# smallDevV1.net
KiCad netlist of a schematic drawn in EAGLE
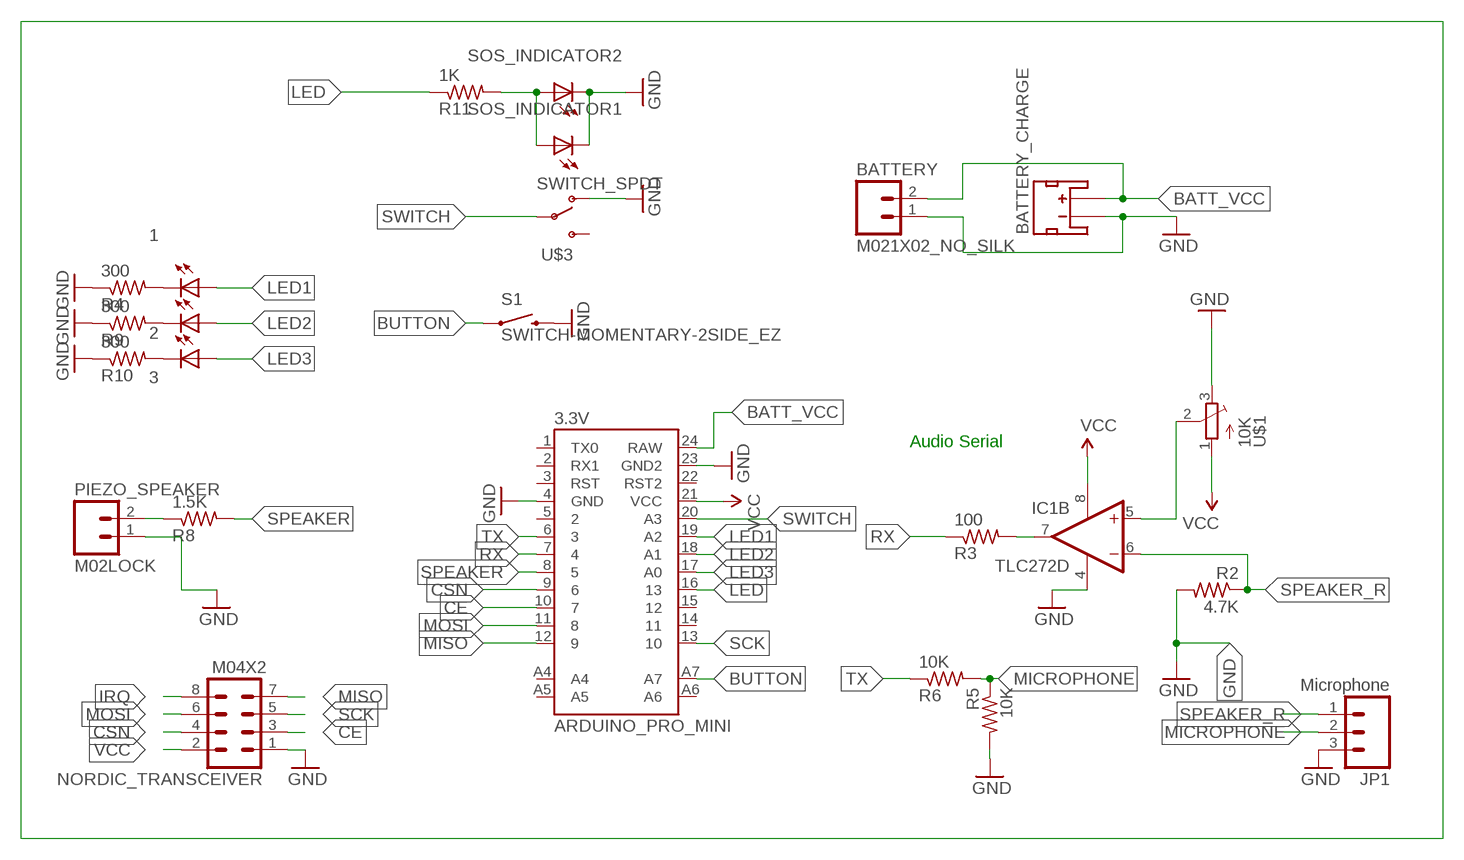
[diagram p0: schematic, sheet 1]

(export (version "E")
  (design (tool "Eeschema 10.0.6"))
  (components
    (comp (ref "1")
      (value "LEDCHIP-LED0805")
      (footprint "eagle-import:CHIP-LED0805")
      (libsource (lib "eagle-import") (part "LEDCHIP-LED0805"))
    )
    (comp (ref "2")
      (value "LEDCHIP-LED0805")
      (footprint "eagle-import:CHIP-LED0805")
      (libsource (lib "eagle-import") (part "LEDCHIP-LED0805"))
    )
    (comp (ref "3")
      (value "LEDCHIP-LED0805")
      (footprint "eagle-import:CHIP-LED0805")
      (libsource (lib "eagle-import") (part "LEDCHIP-LED0805"))
    )
    (comp (ref "3.3V")
      (value "ARDUINO_PRO_MINI")
      (footprint "eagle-import:ARDUINO_PRO_MINI_NO_PROGRAMMING_HEADER")
      (libsource (lib "eagle-import") (part "ARDUINO_PRO_MINI"))
    )
    (comp (ref "BATTERY")
      (value "M021X02_NO_SILK")
      (footprint "eagle-import:1X02_NO_SILK")
      (libsource (lib "eagle-import") (part "M021X02_NO_SILK"))
    )
    (comp (ref "BATTERY_CHARGE")
      (value "JST_2MM_MALE")
      (footprint "eagle-import:JST-2-SMD")
      (libsource (lib "eagle-import") (part "JST_2MM_MALE"))
    )
    (comp (ref "IC1")
      (value "TLC272D")
      (footprint "eagle-import:SO08")
      (libsource (lib "eagle-import") (part "TLC272D"))
    )
    (comp (ref "JP1")
      (value "Microphone")
      (footprint "eagle-import:1X03_LOCK")
      (libsource (lib "eagle-import") (part "M03LOCK"))
    )
    (comp (ref "NORDIC_TRANSCEIVER")
      (value "M04X2")
      (footprint "eagle-import:2X4")
      (libsource (lib "eagle-import") (part "M04X2"))
    )
    (comp (ref "PIEZO_SPEAKER")
      (value "M02LOCK")
      (footprint "eagle-import:1X02_LOCK")
      (libsource (lib "eagle-import") (part "M02LOCK"))
    )
    (comp (ref "R2")
      (value "4.7K")
      (footprint "eagle-import:M0805")
      (libsource (lib "eagle-import") (part "R-US_M0805"))
    )
    (comp (ref "R3")
      (value "100")
      (footprint "eagle-import:M0805")
      (libsource (lib "eagle-import") (part "R-US_M0805"))
    )
    (comp (ref "R4")
      (value "300")
      (footprint "eagle-import:M0805")
      (libsource (lib "eagle-import") (part "R-US_M0805"))
    )
    (comp (ref "R5")
      (value "10K")
      (footprint "eagle-import:M0805")
      (libsource (lib "eagle-import") (part "R-US_M0805"))
    )
    (comp (ref "R6")
      (value "10K")
      (footprint "eagle-import:M0805")
      (libsource (lib "eagle-import") (part "R-US_M0805"))
    )
    (comp (ref "R8")
      (value "1.5K")
      (footprint "eagle-import:M0805")
      (libsource (lib "eagle-import") (part "R-US_M0805"))
    )
    (comp (ref "R9")
      (value "300")
      (footprint "eagle-import:M0805")
      (libsource (lib "eagle-import") (part "R-US_M0805"))
    )
    (comp (ref "R10")
      (value "300")
      (footprint "eagle-import:M0805")
      (libsource (lib "eagle-import") (part "R-US_M0805"))
    )
    (comp (ref "R11")
      (value "1K")
      (footprint "eagle-import:M0805")
      (libsource (lib "eagle-import") (part "R-US_M0805"))
    )
    (comp (ref "S1")
      (value "SWITCH-MOMENTARY-2SIDE_EZ")
      (footprint "eagle-import:TACTILE-PTH-SIDEEZ")
      (libsource (lib "eagle-import") (part "SWITCH-MOMENTARY-2SIDE_EZ"))
    )
    (comp (ref "SOS_INDICATOR1")
      (value "LEDCHIP-LED0805")
      (footprint "eagle-import:CHIP-LED0805")
      (libsource (lib "eagle-import") (part "LEDCHIP-LED0805"))
    )
    (comp (ref "SOS_INDICATOR2")
      (value "LEDCHIP-LED0805")
      (footprint "eagle-import:CHIP-LED0805")
      (libsource (lib "eagle-import") (part "LEDCHIP-LED0805"))
    )
    (comp (ref "U$1")
      (value "10K")
      (footprint "eagle-import:TC33X")
      (libsource (lib "eagle-import") (part "TRIMPOTTC33X"))
    )
    (comp (ref "U$3")
      (value "SWITCH_SPDT")
      (footprint "eagle-import:SWITCH-SPST-SMD-A-NOTHRUHOLE")
      (libsource (lib "eagle-import") (part "SWITCH_SPDT"))
    )
  )
  (nets
    (net (code "1") (name "BATT_VCC") (class "Default")
      (node (ref "3.3V") (pin "24") (pinfunction "RAW_24") (pintype "bidirectional"))
      (node (ref "BATTERY") (pin "2") (pinfunction "2_2") (pintype "passive"))
      (node (ref "BATTERY_CHARGE") (pin "2") (pinfunction "+_2") (pintype "bidirectional"))
    )
    (net (code "2") (name "BUTTON") (class "Default")
      (node (ref "3.3V") (pin "A7") (pinfunction "A7_A7") (pintype "bidirectional"))
      (node (ref "S1") (pin "1") (pinfunction "1_1") (pintype "passive"))
    )
    (net (code "3") (name "CE") (class "Default")
      (node (ref "3.3V") (pin "10") (pinfunction "7_10") (pintype "bidirectional"))
      (node (ref "NORDIC_TRANSCEIVER") (pin "3") (pinfunction "3_3") (pintype "passive"))
    )
    (net (code "4") (name "CSN") (class "Default")
      (node (ref "3.3V") (pin "9") (pinfunction "6_9") (pintype "bidirectional"))
      (node (ref "NORDIC_TRANSCEIVER") (pin "4") (pinfunction "4_4") (pintype "passive"))
    )
    (net (code "5") (name "GND") (class "Default")
      (node (ref "3.3V") (pin "23") (pinfunction "GND2_23") (pintype "bidirectional"))
      (node (ref "3.3V") (pin "4") (pinfunction "GND_4") (pintype "bidirectional"))
      (node (ref "BATTERY") (pin "1") (pinfunction "1_1") (pintype "passive"))
      (node (ref "BATTERY_CHARGE") (pin "1") (pinfunction "-_1") (pintype "bidirectional"))
      (node (ref "IC1") (pin "4") (pinfunction "V-_4") (pintype "power_in"))
      (node (ref "JP1") (pin "3") (pinfunction "3_3") (pintype "passive"))
      (node (ref "NORDIC_TRANSCEIVER") (pin "1") (pinfunction "1_1") (pintype "passive"))
      (node (ref "PIEZO_SPEAKER") (pin "1") (pinfunction "1_1") (pintype "passive"))
      (node (ref "R10") (pin "1") (pinfunction "1_1") (pintype "passive"))
      (node (ref "R2") (pin "2") (pinfunction "2_2") (pintype "passive"))
      (node (ref "R4") (pin "1") (pinfunction "1_1") (pintype "passive"))
      (node (ref "R5") (pin "2") (pinfunction "2_2") (pintype "passive"))
      (node (ref "R9") (pin "1") (pinfunction "1_1") (pintype "passive"))
      (node (ref "S1") (pin "2") (pinfunction "2_2") (pintype "passive"))
      (node (ref "SOS_INDICATOR1") (pin "C") (pinfunction "C_C") (pintype "passive"))
      (node (ref "SOS_INDICATOR2") (pin "C") (pinfunction "C_C") (pintype "passive"))
      (node (ref "U$1") (pin "3") (pinfunction "E_3") (pintype "passive"))
      (node (ref "U$3") (pin "1") (pinfunction "O_1") (pintype "passive"))
    )
    (net (code "6") (name "IRQ") (class "Default")
      (node (ref "NORDIC_TRANSCEIVER") (pin "8") (pinfunction "8_8") (pintype "passive"))
    )
    (net (code "7") (name "LED") (class "Default")
      (node (ref "3.3V") (pin "16") (pinfunction "13_16") (pintype "bidirectional"))
      (node (ref "R11") (pin "1") (pinfunction "1_1") (pintype "passive"))
    )
    (net (code "8") (name "LED1") (class "Default")
      (node (ref "1") (pin "A") (pinfunction "A_A") (pintype "passive"))
      (node (ref "3.3V") (pin "19") (pinfunction "A2_19") (pintype "bidirectional"))
    )
    (net (code "9") (name "LED2") (class "Default")
      (node (ref "2") (pin "A") (pinfunction "A_A") (pintype "passive"))
      (node (ref "3.3V") (pin "18") (pinfunction "A1_18") (pintype "bidirectional"))
    )
    (net (code "10") (name "LED3") (class "Default")
      (node (ref "3") (pin "A") (pinfunction "A_A") (pintype "passive"))
      (node (ref "3.3V") (pin "17") (pinfunction "A0_17") (pintype "bidirectional"))
    )
    (net (code "11") (name "MICROPHONE") (class "Default")
      (node (ref "JP1") (pin "2") (pinfunction "2_2") (pintype "passive"))
      (node (ref "R5") (pin "1") (pinfunction "1_1") (pintype "passive"))
      (node (ref "R6") (pin "2") (pinfunction "2_2") (pintype "passive"))
    )
    (net (code "12") (name "MISO") (class "Default")
      (node (ref "3.3V") (pin "12") (pinfunction "9_12") (pintype "bidirectional"))
      (node (ref "NORDIC_TRANSCEIVER") (pin "7") (pinfunction "7_7") (pintype "passive"))
    )
    (net (code "13") (name "MOSI") (class "Default")
      (node (ref "3.3V") (pin "11") (pinfunction "8_11") (pintype "bidirectional"))
      (node (ref "NORDIC_TRANSCEIVER") (pin "6") (pinfunction "6_6") (pintype "passive"))
    )
    (net (code "14") (name "Net-(1-PadC)") (class "Default")
      (node (ref "1") (pin "C") (pinfunction "C_C") (pintype "passive"))
      (node (ref "R4") (pin "2") (pinfunction "2_2") (pintype "passive"))
    )
    (net (code "15") (name "Net-(2-PadC)") (class "Default")
      (node (ref "2") (pin "C") (pinfunction "C_C") (pintype "passive"))
      (node (ref "R9") (pin "2") (pinfunction "2_2") (pintype "passive"))
    )
    (net (code "16") (name "Net-(3-PadC)") (class "Default")
      (node (ref "3") (pin "C") (pinfunction "C_C") (pintype "passive"))
      (node (ref "R10") (pin "2") (pinfunction "2_2") (pintype "passive"))
    )
    (net (code "17") (name "Net-(IC1B-+IN)") (class "Default")
      (node (ref "IC1") (pin "5") (pinfunction "+IN_5") (pintype "input"))
      (node (ref "U$1") (pin "2") (pinfunction "S_2") (pintype "passive"))
    )
    (net (code "18") (name "Net-(IC1B-OUT)") (class "Default")
      (node (ref "IC1") (pin "7") (pinfunction "OUT_7") (pintype "output"))
      (node (ref "R3") (pin "2") (pinfunction "2_2") (pintype "passive"))
    )
    (net (code "19") (name "Net-(PIEZO_SPEAKER-Pad2)") (class "Default")
      (node (ref "PIEZO_SPEAKER") (pin "2") (pinfunction "2_2") (pintype "passive"))
      (node (ref "R8") (pin "1") (pinfunction "1_1") (pintype "passive"))
    )
    (net (code "20") (name "Net-(R11-Pad2)") (class "Default")
      (node (ref "R11") (pin "2") (pinfunction "2_2") (pintype "passive"))
      (node (ref "SOS_INDICATOR1") (pin "A") (pinfunction "A_A") (pintype "passive"))
      (node (ref "SOS_INDICATOR2") (pin "A") (pinfunction "A_A") (pintype "passive"))
    )
    (net (code "21") (name "RX") (class "Default")
      (node (ref "3.3V") (pin "7") (pinfunction "4_7") (pintype "bidirectional"))
      (node (ref "R3") (pin "1") (pinfunction "1_1") (pintype "passive"))
    )
    (net (code "22") (name "SCK") (class "Default")
      (node (ref "3.3V") (pin "13") (pinfunction "10_13") (pintype "bidirectional"))
      (node (ref "NORDIC_TRANSCEIVER") (pin "5") (pinfunction "5_5") (pintype "passive"))
    )
    (net (code "23") (name "SPEAKER") (class "Default")
      (node (ref "3.3V") (pin "8") (pinfunction "5_8") (pintype "bidirectional"))
      (node (ref "R8") (pin "2") (pinfunction "2_2") (pintype "passive"))
    )
    (net (code "24") (name "SPEAKER_R") (class "Default")
      (node (ref "IC1") (pin "6") (pinfunction "-IN_6") (pintype "input"))
      (node (ref "JP1") (pin "1") (pinfunction "1_1") (pintype "passive"))
      (node (ref "R2") (pin "1") (pinfunction "1_1") (pintype "passive"))
    )
    (net (code "25") (name "SWITCH") (class "Default")
      (node (ref "3.3V") (pin "20") (pinfunction "A3_20") (pintype "bidirectional"))
      (node (ref "U$3") (pin "2") (pinfunction "P_2") (pintype "passive"))
    )
    (net (code "26") (name "TX") (class "Default")
      (node (ref "3.3V") (pin "6") (pinfunction "3_6") (pintype "bidirectional"))
      (node (ref "R6") (pin "1") (pinfunction "1_1") (pintype "passive"))
    )
    (net (code "27") (name "VCC") (class "Default")
      (node (ref "3.3V") (pin "21") (pinfunction "VCC_21") (pintype "bidirectional"))
      (node (ref "IC1") (pin "8") (pinfunction "V+_8") (pintype "power_in"))
      (node (ref "NORDIC_TRANSCEIVER") (pin "2") (pinfunction "2_2") (pintype "passive"))
      (node (ref "U$1") (pin "1") (pinfunction "A_1") (pintype "passive"))
    )
    (net (code "28") (name "unconnected-(3.3V-2-Pad5)") (class "Default")
      (node (ref "3.3V") (pin "5") (pinfunction "2_5") (pintype "bidirectional"))
    )
    (net (code "29") (name "unconnected-(3.3V-11-Pad14)") (class "Default")
      (node (ref "3.3V") (pin "14") (pinfunction "11_14") (pintype "bidirectional"))
    )
    (net (code "30") (name "unconnected-(3.3V-12-Pad15)") (class "Default")
      (node (ref "3.3V") (pin "15") (pinfunction "12_15") (pintype "bidirectional"))
    )
    (net (code "31") (name "unconnected-(3.3V-PadA4)") (class "Default")
      (node (ref "3.3V") (pin "A4") (pinfunction "A4_A4") (pintype "bidirectional"))
    )
    (net (code "32") (name "unconnected-(3.3V-PadA5)") (class "Default")
      (node (ref "3.3V") (pin "A5") (pinfunction "A5_A5") (pintype "bidirectional"))
    )
    (net (code "33") (name "unconnected-(3.3V-PadA6)") (class "Default")
      (node (ref "3.3V") (pin "A6") (pinfunction "A6_A6") (pintype "bidirectional"))
    )
    (net (code "34") (name "unconnected-(3.3V-RST-Pad3)") (class "Default")
      (node (ref "3.3V") (pin "3") (pinfunction "RST_3") (pintype "bidirectional"))
    )
    (net (code "35") (name "unconnected-(3.3V-RST2-Pad22)") (class "Default")
      (node (ref "3.3V") (pin "22") (pinfunction "RST2_22") (pintype "bidirectional"))
    )
    (net (code "36") (name "unconnected-(3.3V-RX1-Pad2)") (class "Default")
      (node (ref "3.3V") (pin "2") (pinfunction "RX1_2") (pintype "bidirectional"))
    )
    (net (code "37") (name "unconnected-(3.3V-TX0-Pad1)") (class "Default")
      (node (ref "3.3V") (pin "1") (pinfunction "TX0_1") (pintype "bidirectional"))
    )
    (net (code "38") (name "unconnected-(BATTERY_CHARGE-PAD1-PadNC1)") (class "Default")
      (node (ref "BATTERY_CHARGE") (pin "NC1") (pinfunction "PAD1_NC1") (pintype "bidirectional"))
    )
    (net (code "39") (name "unconnected-(BATTERY_CHARGE-PAD2-PadNC2)") (class "Default")
      (node (ref "BATTERY_CHARGE") (pin "NC2") (pinfunction "PAD2_NC2") (pintype "bidirectional"))
    )
    (net (code "40") (name "unconnected-(U$3-S-Pad3)") (class "Default")
      (node (ref "U$3") (pin "3") (pinfunction "S_3") (pintype "passive"))
    )
  )
)
